# 2025-09-03.net
KiCad netlist of a schematic drawn in Altium Designer
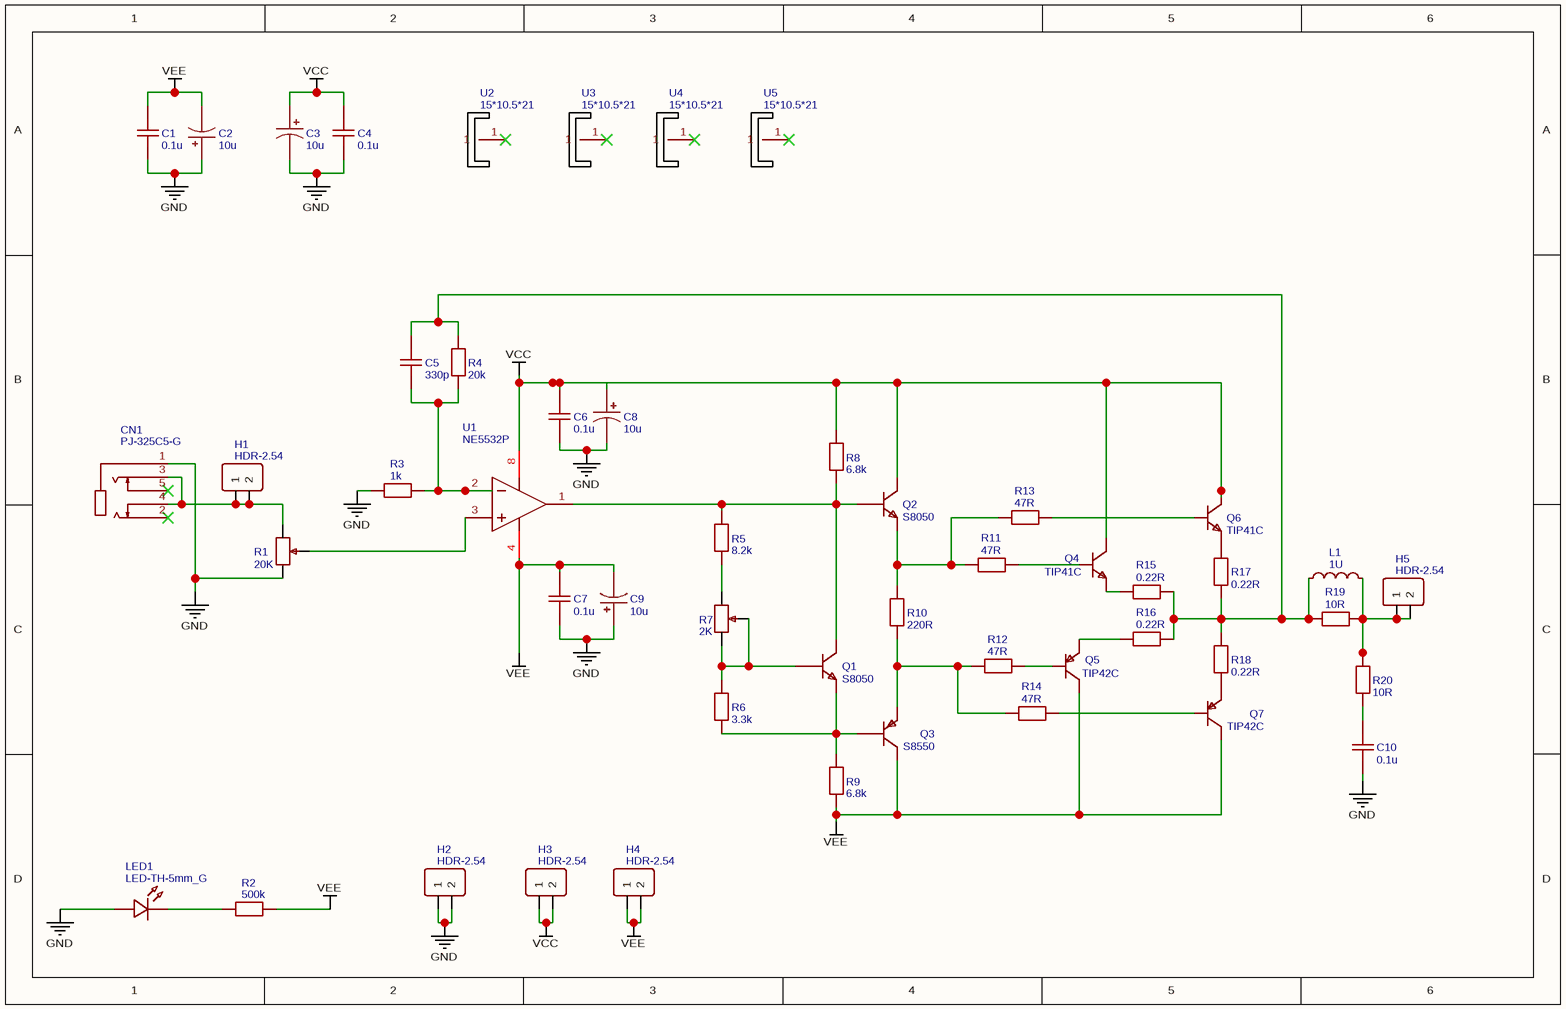
[diagram p0: 原理图_模电_2025-09-03.schdoc]

(export (version "E")
  (design (tool "Eeschema 10.0.6"))
  (components
    (comp (ref "C1")
      (value "0.1u")
      (fields (field (name "CONTRIBUTOR") "LCEDA_Lib"))
      (libsource (lib "altium-import") (part "root_1_0.1u_"))
    )
    (comp (ref "C2")
      (value "10u")
      (fields (field (name "CONTRIBUTOR") "LCEDA_Lib"))
      (libsource (lib "altium-import") (part "root_1_10u_"))
    )
    (comp (ref "C3")
      (value "10u")
      (fields (field (name "CONTRIBUTOR") "LCEDA_Lib"))
      (libsource (lib "altium-import") (part "root_3_10u_"))
    )
    (comp (ref "C4")
      (value "0.1u")
      (fields (field (name "CONTRIBUTOR") "LCEDA_Lib"))
      (libsource (lib "altium-import") (part "root_3_0.1u_"))
    )
    (comp (ref "C5")
      (value "330p")
      (fields (field (name "CONTRIBUTOR") "LCEDA_Lib"))
      (libsource (lib "altium-import") (part "root_1_330p_"))
    )
    (comp (ref "C6")
      (value "0.1u")
      (fields (field (name "CONTRIBUTOR") "LCEDA_Lib"))
      (libsource (lib "altium-import") (part "root_1_0.1u_"))
    )
    (comp (ref "C7")
      (value "0.1u")
      (fields (field (name "CONTRIBUTOR") "LCEDA_Lib"))
      (libsource (lib "altium-import") (part "root_1_0.1u_"))
    )
    (comp (ref "C8")
      (value "10u")
      (fields (field (name "CONTRIBUTOR") "LCEDA_Lib"))
      (libsource (lib "altium-import") (part "root_3_10u_"))
    )
    (comp (ref "C9")
      (value "10u")
      (fields (field (name "CONTRIBUTOR") "LCEDA_Lib"))
      (libsource (lib "altium-import") (part "root_1_10u_"))
    )
    (comp (ref "C10")
      (value "0.1u")
      (fields (field (name "CONTRIBUTOR") "LCEDA_Lib"))
      (libsource (lib "altium-import") (part "root_1_0.1u_"))
    )
    (comp (ref "CN1")
      (value "PJ-325C5-G")
      (fields (field (name "MANUFACTURER") "XKB Connectivity") (field (name "CONTRIBUTOR") "LCSC"))
      (libsource (lib "altium-import") (part "root_0_PJ-325C5-G_"))
    )
    (comp (ref "H1")
      (value "HDR-2.54")
      (fields (field (name "CONTRIBUTOR") "LCEDA_Lib"))
      (libsource (lib "altium-import") (part "root_1_HDR-2.54_"))
    )
    (comp (ref "H2")
      (value "HDR-2.54")
      (fields (field (name "CONTRIBUTOR") "LCEDA_Lib"))
      (libsource (lib "altium-import") (part "root_1_HDR-2.54_"))
    )
    (comp (ref "H3")
      (value "HDR-2.54")
      (fields (field (name "CONTRIBUTOR") "LCEDA_Lib"))
      (libsource (lib "altium-import") (part "root_1_HDR-2.54_"))
    )
    (comp (ref "H4")
      (value "HDR-2.54")
      (fields (field (name "CONTRIBUTOR") "LCEDA_Lib"))
      (libsource (lib "altium-import") (part "root_1_HDR-2.54_"))
    )
    (comp (ref "H5")
      (value "HDR-2.54")
      (fields (field (name "CONTRIBUTOR") "LCEDA_Lib"))
      (libsource (lib "altium-import") (part "root_1_HDR-2.54_"))
    )
    (comp (ref "L1")
      (value "1U")
      (fields (field (name "CONTRIBUTOR") "LCEDA_Lib"))
      (libsource (lib "altium-import") (part "root_0_1U_"))
    )
    (comp (ref "LED1")
      (value "LED-TH-5mm_G")
      (fields
        (field (name "MANUFACTURER") "EVERLIGHT(台湾亿光)")
        (field (name "MANUFACTURER PART") "333-2SYGD/S530-E2")
        (field (name "CONTRIBUTOR") "LCEDA_Lib")
      )
      (libsource (lib "altium-import") (part "root_0_LED-TH-5mm_G_"))
    )
    (comp (ref "Q1")
      (value "S8050")
      (fields (field (name "MANUFACTURER") "CJ") (field (name "CONTRIBUTOR") "立创EDA官方封装库"))
      (libsource (lib "altium-import") (part "root_0_S8050_"))
    )
    (comp (ref "Q2")
      (value "S8050")
      (fields (field (name "MANUFACTURER") "CJ") (field (name "CONTRIBUTOR") "立创EDA官方封装库"))
      (libsource (lib "altium-import") (part "root_0_S8050_"))
    )
    (comp (ref "Q3")
      (value "S8550")
      (fields (field (name "MANUFACTURER") "CJ") (field (name "CONTRIBUTOR") "LCSC"))
      (libsource (lib "altium-import") (part "root_2_S8550_"))
    )
    (comp (ref "Q4")
      (value "TIP41C")
      (fields (field (name "MANUFACTURER") "CJ"))
      (libsource (lib "altium-import") (part "root_0_TIP41C_"))
    )
    (comp (ref "Q5")
      (value "TIP42C")
      (fields (field (name "MANUFACTURER") "CJ"))
      (libsource (lib "altium-import") (part "root_2_TIP42C_"))
    )
    (comp (ref "Q6")
      (value "TIP41C")
      (fields (field (name "MANUFACTURER") "CJ"))
      (libsource (lib "altium-import") (part "root_0_TIP41C_"))
    )
    (comp (ref "Q7")
      (value "TIP42C")
      (fields (field (name "MANUFACTURER") "CJ"))
      (libsource (lib "altium-import") (part "root_2_TIP42C_"))
    )
    (comp (ref "R1")
      (value "20K")
      (fields
        (field (name "MANUFACTURER") "PANASONIC")
        (field (name "MANUFACTURER PART") "EVND8AA03B24")
        (field (name "CONTRIBUTOR") "LCSC")
      )
      (libsource (lib "altium-import") (part "root_2_20K_"))
    )
    (comp (ref "R2")
      (value "500k")
      (fields (field (name "CONTRIBUTOR") "LCEDA_Lib"))
      (libsource (lib "altium-import") (part "root_0_500k_"))
    )
    (comp (ref "R3")
      (value "1k")
      (fields (field (name "CONTRIBUTOR") "LCEDA_Lib"))
      (libsource (lib "altium-import") (part "root_0_1k_"))
    )
    (comp (ref "R4")
      (value "20k")
      (fields (field (name "CONTRIBUTOR") "LCEDA_Lib"))
      (libsource (lib "altium-import") (part "root_1_20k_"))
    )
    (comp (ref "R5")
      (value "8.2k")
      (fields (field (name "CONTRIBUTOR") "LCEDA_Lib"))
      (libsource (lib "altium-import") (part "root_1_8.2k_"))
    )
    (comp (ref "R6")
      (value "3.3k")
      (fields (field (name "CONTRIBUTOR") "LCEDA_Lib"))
      (libsource (lib "altium-import") (part "root_1_3.3k_"))
    )
    (comp (ref "R7")
      (value "2K")
      (fields
        (field (name "MANUFACTURER") "HDK")
        (field (name "MANUFACTURER PART") "VZ067TL1B202")
        (field (name "CONTRIBUTOR") "LCSC")
      )
      (libsource (lib "altium-import") (part "root_3_2K_"))
    )
    (comp (ref "R8")
      (value "6.8k")
      (fields (field (name "CONTRIBUTOR") "LCEDA_Lib"))
      (libsource (lib "altium-import") (part "root_1_6.8k_"))
    )
    (comp (ref "R9")
      (value "6.8k")
      (fields (field (name "CONTRIBUTOR") "LCEDA_Lib"))
      (libsource (lib "altium-import") (part "root_1_6.8k_"))
    )
    (comp (ref "R10")
      (value "220R")
      (fields (field (name "CONTRIBUTOR") "LCEDA_Lib"))
      (libsource (lib "altium-import") (part "root_1_220R_"))
    )
    (comp (ref "R11")
      (value "47R")
      (fields (field (name "CONTRIBUTOR") "LCEDA_Lib"))
      (libsource (lib "altium-import") (part "root_2_47R_"))
    )
    (comp (ref "R12")
      (value "47R")
      (fields (field (name "CONTRIBUTOR") "LCEDA_Lib"))
      (libsource (lib "altium-import") (part "root_2_47R_"))
    )
    (comp (ref "R13")
      (value "47R")
      (fields (field (name "CONTRIBUTOR") "LCEDA_Lib"))
      (libsource (lib "altium-import") (part "root_2_47R_"))
    )
    (comp (ref "R14")
      (value "47R")
      (fields (field (name "CONTRIBUTOR") "LCEDA_Lib"))
      (libsource (lib "altium-import") (part "root_2_47R_"))
    )
    (comp (ref "R15")
      (value "0.22R")
      (fields (field (name "CONTRIBUTOR") "LCEDA_Lib"))
      (libsource (lib "altium-import") (part "root_2_0.22R_"))
    )
    (comp (ref "R16")
      (value "0.22R")
      (fields (field (name "CONTRIBUTOR") "LCEDA_Lib"))
      (libsource (lib "altium-import") (part "root_2_0.22R_"))
    )
    (comp (ref "R17")
      (value "0.22R")
      (fields (field (name "CONTRIBUTOR") "LCEDA_Lib"))
      (libsource (lib "altium-import") (part "root_3_0.22R_"))
    )
    (comp (ref "R18")
      (value "0.22R")
      (fields (field (name "CONTRIBUTOR") "LCEDA_Lib"))
      (libsource (lib "altium-import") (part "root_3_0.22R_"))
    )
    (comp (ref "R19")
      (value "10R")
      (fields (field (name "CONTRIBUTOR") "LCEDA_Lib"))
      (libsource (lib "altium-import") (part "root_2_10R_"))
    )
    (comp (ref "R20")
      (value "10R")
      (fields (field (name "CONTRIBUTOR") "LCEDA_Lib"))
      (libsource (lib "altium-import") (part "root_3_10R_"))
    )
    (comp (ref "U1")
      (value "NE5532P")
      (fields (field (name "MANUFACTURER") "TI") (field (name "SUBPART_NO") "1"))
      (libsource (lib "altium-import") (part "root_0_NE5532P_"))
    )
    (comp (ref "U2")
      (value "15*10.5*21")
      (fields (field (name "MANUFACTURER") "Made in China") (field (name "CONTRIBUTOR") "LCSC"))
      (libsource (lib "altium-import") (part "root_1_15*10.5*21_"))
    )
    (comp (ref "U3")
      (value "15*10.5*21")
      (fields (field (name "MANUFACTURER") "Made in China") (field (name "CONTRIBUTOR") "LCSC"))
      (libsource (lib "altium-import") (part "root_1_15*10.5*21_"))
    )
    (comp (ref "U4")
      (value "15*10.5*21")
      (fields (field (name "MANUFACTURER") "Made in China") (field (name "CONTRIBUTOR") "LCSC"))
      (libsource (lib "altium-import") (part "root_1_15*10.5*21_"))
    )
    (comp (ref "U5")
      (value "15*10.5*21")
      (fields (field (name "MANUFACTURER") "Made in China") (field (name "CONTRIBUTOR") "LCSC"))
      (libsource (lib "altium-import") (part "root_1_15*10.5*21_"))
    )
  )
  (nets
    (net (code "1") (name "GND") (class "Default")
      (node (ref "C1") (pin "1") (pinfunction "1_1") (pintype "passive"))
      (node (ref "C10") (pin "1") (pinfunction "1_1") (pintype "passive"))
      (node (ref "C2") (pin "1") (pinfunction "1_1") (pintype "passive"))
      (node (ref "C3") (pin "2") (pinfunction "2_2") (pintype "passive"))
      (node (ref "C4") (pin "2") (pinfunction "2_2") (pintype "passive"))
      (node (ref "C6") (pin "1") (pinfunction "1_1") (pintype "passive"))
      (node (ref "C7") (pin "1") (pinfunction "1_1") (pintype "passive"))
      (node (ref "C8") (pin "2") (pinfunction "2_2") (pintype "passive"))
      (node (ref "C9") (pin "1") (pinfunction "1_1") (pintype "passive"))
      (node (ref "CN1") (pin "1") (pinfunction "1_1") (pintype "passive"))
      (node (ref "H2") (pin "1") (pinfunction "1_1") (pintype "passive"))
      (node (ref "H2") (pin "2") (pinfunction "2_2") (pintype "passive"))
      (node (ref "LED1") (pin "1") (pinfunction "1_1") (pintype "passive"))
      (node (ref "R1") (pin "1") (pinfunction "1_1") (pintype "passive"))
      (node (ref "R3") (pin "1") (pinfunction "1_1") (pintype "passive"))
    )
    (net (code "2") (name "Net-(C5-Pad2)") (class "Default")
      (node (ref "C5") (pin "2") (pinfunction "2_2") (pintype "passive"))
      (node (ref "L1") (pin "1") (pinfunction "1_1") (pintype "passive"))
      (node (ref "R15") (pin "1") (pinfunction "1_1") (pintype "passive"))
      (node (ref "R16") (pin "1") (pinfunction "1_1") (pintype "passive"))
      (node (ref "R17") (pin "2") (pinfunction "2_2") (pintype "passive"))
      (node (ref "R18") (pin "1") (pinfunction "1_1") (pintype "passive"))
      (node (ref "R19") (pin "2") (pinfunction "2_2") (pintype "passive"))
      (node (ref "R4") (pin "2") (pinfunction "2_2") (pintype "passive"))
    )
    (net (code "3") (name "Net-(C10-Pad2)") (class "Default")
      (node (ref "C10") (pin "2") (pinfunction "2_2") (pintype "passive"))
      (node (ref "R20") (pin "2") (pinfunction "2_2") (pintype "passive"))
    )
    (net (code "4") (name "Net-(CN1-Pad3)") (class "Default")
      (node (ref "CN1") (pin "3") (pinfunction "3_3") (pintype "passive"))
      (node (ref "CN1") (pin "4") (pinfunction "4_4") (pintype "passive"))
      (node (ref "H1") (pin "1") (pinfunction "1_1") (pintype "passive"))
      (node (ref "H1") (pin "2") (pinfunction "2_2") (pintype "passive"))
      (node (ref "R1") (pin "3") (pinfunction "3_3") (pintype "passive"))
    )
    (net (code "5") (name "Net-(H5-Pad1)") (class "Default")
      (node (ref "H5") (pin "1") (pinfunction "1_1") (pintype "passive"))
      (node (ref "H5") (pin "2") (pinfunction "2_2") (pintype "passive"))
      (node (ref "L1") (pin "2") (pinfunction "2_2") (pintype "passive"))
      (node (ref "R19") (pin "1") (pinfunction "1_1") (pintype "passive"))
      (node (ref "R20") (pin "1") (pinfunction "1_1") (pintype "passive"))
    )
    (net (code "6") (name "Net-(LED1-Pad2)") (class "Default")
      (node (ref "LED1") (pin "2") (pinfunction "2_2") (pintype "passive"))
      (node (ref "R2") (pin "1") (pinfunction "1_1") (pintype "passive"))
    )
    (net (code "7") (name "Net-(Q1-B)") (class "Default")
      (node (ref "Q1") (pin "2") (pinfunction "B_2") (pintype "passive"))
      (node (ref "R6") (pin "2") (pinfunction "2_2") (pintype "passive"))
      (node (ref "R7") (pin "2") (pinfunction "2_2") (pintype "passive"))
      (node (ref "R7") (pin "3") (pinfunction "3_3") (pintype "passive"))
    )
    (net (code "8") (name "Net-(Q1-C)") (class "Default")
      (node (ref "Q1") (pin "3") (pinfunction "C_3") (pintype "passive"))
      (node (ref "Q2") (pin "2") (pinfunction "B_2") (pintype "passive"))
      (node (ref "R5") (pin "2") (pinfunction "2_2") (pintype "passive"))
      (node (ref "R8") (pin "1") (pinfunction "1_1") (pintype "passive"))
      (node (ref "U1") (pin "1") (pinfunction "OUT1_1") (pintype "passive"))
    )
    (net (code "9") (name "Net-(Q1-E)") (class "Default")
      (node (ref "Q1") (pin "1") (pinfunction "E_1") (pintype "passive"))
      (node (ref "Q3") (pin "2") (pinfunction "B_2") (pintype "passive"))
      (node (ref "R6") (pin "1") (pinfunction "1_1") (pintype "passive"))
      (node (ref "R9") (pin "2") (pinfunction "2_2") (pintype "passive"))
    )
    (net (code "10") (name "Net-(Q2-E)") (class "Default")
      (node (ref "Q2") (pin "1") (pinfunction "E_1") (pintype "passive"))
      (node (ref "R10") (pin "2") (pinfunction "2_2") (pintype "passive"))
      (node (ref "R11") (pin "2") (pinfunction "2_2") (pintype "passive"))
      (node (ref "R13") (pin "2") (pinfunction "2_2") (pintype "passive"))
    )
    (net (code "11") (name "Net-(Q3-E)") (class "Default")
      (node (ref "Q3") (pin "1") (pinfunction "E_1") (pintype "passive"))
      (node (ref "R10") (pin "1") (pinfunction "1_1") (pintype "passive"))
      (node (ref "R12") (pin "2") (pinfunction "2_2") (pintype "passive"))
      (node (ref "R14") (pin "2") (pinfunction "2_2") (pintype "passive"))
    )
    (net (code "12") (name "Net-(Q4-B)") (class "Default")
      (node (ref "Q4") (pin "1") (pinfunction "B_1") (pintype "passive"))
      (node (ref "R11") (pin "1") (pinfunction "1_1") (pintype "passive"))
    )
    (net (code "13") (name "Net-(Q4-E)") (class "Default")
      (node (ref "Q4") (pin "3") (pinfunction "E_3") (pintype "passive"))
      (node (ref "R15") (pin "2") (pinfunction "2_2") (pintype "passive"))
    )
    (net (code "14") (name "Net-(Q5-B)") (class "Default")
      (node (ref "Q5") (pin "1") (pinfunction "B_1") (pintype "passive"))
      (node (ref "R12") (pin "1") (pinfunction "1_1") (pintype "passive"))
    )
    (net (code "15") (name "Net-(Q5-E)") (class "Default")
      (node (ref "Q5") (pin "3") (pinfunction "E_3") (pintype "passive"))
      (node (ref "R16") (pin "2") (pinfunction "2_2") (pintype "passive"))
    )
    (net (code "16") (name "Net-(Q6-B)") (class "Default")
      (node (ref "Q6") (pin "1") (pinfunction "B_1") (pintype "passive"))
      (node (ref "R13") (pin "1") (pinfunction "1_1") (pintype "passive"))
    )
    (net (code "17") (name "Net-(Q6-E)") (class "Default")
      (node (ref "Q6") (pin "3") (pinfunction "E_3") (pintype "passive"))
      (node (ref "R17") (pin "1") (pinfunction "1_1") (pintype "passive"))
    )
    (net (code "18") (name "Net-(Q7-B)") (class "Default")
      (node (ref "Q7") (pin "1") (pinfunction "B_1") (pintype "passive"))
      (node (ref "R14") (pin "1") (pinfunction "1_1") (pintype "passive"))
    )
    (net (code "19") (name "Net-(Q7-E)") (class "Default")
      (node (ref "Q7") (pin "3") (pinfunction "E_3") (pintype "passive"))
      (node (ref "R18") (pin "2") (pinfunction "2_2") (pintype "passive"))
    )
    (net (code "20") (name "Net-(R5-Pad1)") (class "Default")
      (node (ref "R5") (pin "1") (pinfunction "1_1") (pintype "passive"))
      (node (ref "R7") (pin "1") (pinfunction "1_1") (pintype "passive"))
    )
    (net (code "21") (name "Net-(U1-IN1+)") (class "Default")
      (node (ref "R1") (pin "2") (pinfunction "2_2") (pintype "passive"))
      (node (ref "U1") (pin "3") (pinfunction "IN1+_3") (pintype "passive"))
    )
    (net (code "22") (name "Net-(U1-IN1-)") (class "Default")
      (node (ref "C5") (pin "1") (pinfunction "1_1") (pintype "passive"))
      (node (ref "R3") (pin "2") (pinfunction "2_2") (pintype "passive"))
      (node (ref "R4") (pin "1") (pinfunction "1_1") (pintype "passive"))
      (node (ref "U1") (pin "2") (pinfunction "IN1-_2") (pintype "passive"))
    )
    (net (code "23") (name "VCC") (class "Default")
      (node (ref "C3") (pin "1") (pinfunction "1_1") (pintype "passive"))
      (node (ref "C4") (pin "1") (pinfunction "1_1") (pintype "passive"))
      (node (ref "C6") (pin "2") (pinfunction "2_2") (pintype "passive"))
      (node (ref "C8") (pin "1") (pinfunction "1_1") (pintype "passive"))
      (node (ref "H3") (pin "1") (pinfunction "1_1") (pintype "passive"))
      (node (ref "H3") (pin "2") (pinfunction "2_2") (pintype "passive"))
      (node (ref "Q2") (pin "3") (pinfunction "C_3") (pintype "passive"))
      (node (ref "Q4") (pin "2") (pinfunction "C_2") (pintype "passive"))
      (node (ref "Q6") (pin "2") (pinfunction "C_2") (pintype "passive"))
      (node (ref "R8") (pin "2") (pinfunction "2_2") (pintype "passive"))
      (node (ref "U1") (pin "8") (pinfunction "VCC+_8") (pintype "passive"))
    )
    (net (code "24") (name "VEE") (class "Default")
      (node (ref "C1") (pin "2") (pinfunction "2_2") (pintype "passive"))
      (node (ref "C2") (pin "2") (pinfunction "2_2") (pintype "passive"))
      (node (ref "C7") (pin "2") (pinfunction "2_2") (pintype "passive"))
      (node (ref "C9") (pin "2") (pinfunction "2_2") (pintype "passive"))
      (node (ref "H4") (pin "1") (pinfunction "1_1") (pintype "passive"))
      (node (ref "H4") (pin "2") (pinfunction "2_2") (pintype "passive"))
      (node (ref "Q3") (pin "3") (pinfunction "C_3") (pintype "passive"))
      (node (ref "Q5") (pin "2") (pinfunction "C_2") (pintype "passive"))
      (node (ref "Q7") (pin "2") (pinfunction "C_2") (pintype "passive"))
      (node (ref "R2") (pin "2") (pinfunction "2_2") (pintype "passive"))
      (node (ref "R9") (pin "1") (pinfunction "1_1") (pintype "passive"))
      (node (ref "U1") (pin "4") (pinfunction "VCC-_4") (pintype "passive"))
    )
    (net (code "25") (name "unconnected-(CN1-Pad2)") (class "Default")
      (node (ref "CN1") (pin "2") (pinfunction "2_2") (pintype "passive+no_connect"))
    )
    (net (code "26") (name "unconnected-(CN1-Pad5)") (class "Default")
      (node (ref "CN1") (pin "5") (pinfunction "5_5") (pintype "passive+no_connect"))
    )
    (net (code "27") (name "unconnected-(U2-Pad1)") (class "Default")
      (node (ref "U2") (pin "1") (pinfunction "1_1") (pintype "passive+no_connect"))
    )
    (net (code "28") (name "unconnected-(U3-Pad1)") (class "Default")
      (node (ref "U3") (pin "1") (pinfunction "1_1") (pintype "passive+no_connect"))
    )
    (net (code "29") (name "unconnected-(U4-Pad1)") (class "Default")
      (node (ref "U4") (pin "1") (pinfunction "1_1") (pintype "passive+no_connect"))
    )
    (net (code "30") (name "unconnected-(U5-Pad1)") (class "Default")
      (node (ref "U5") (pin "1") (pinfunction "1_1") (pintype "passive+no_connect"))
    )
  )
)
